# circuit.net
KiCad netlist of a schematic drawn in EAGLE
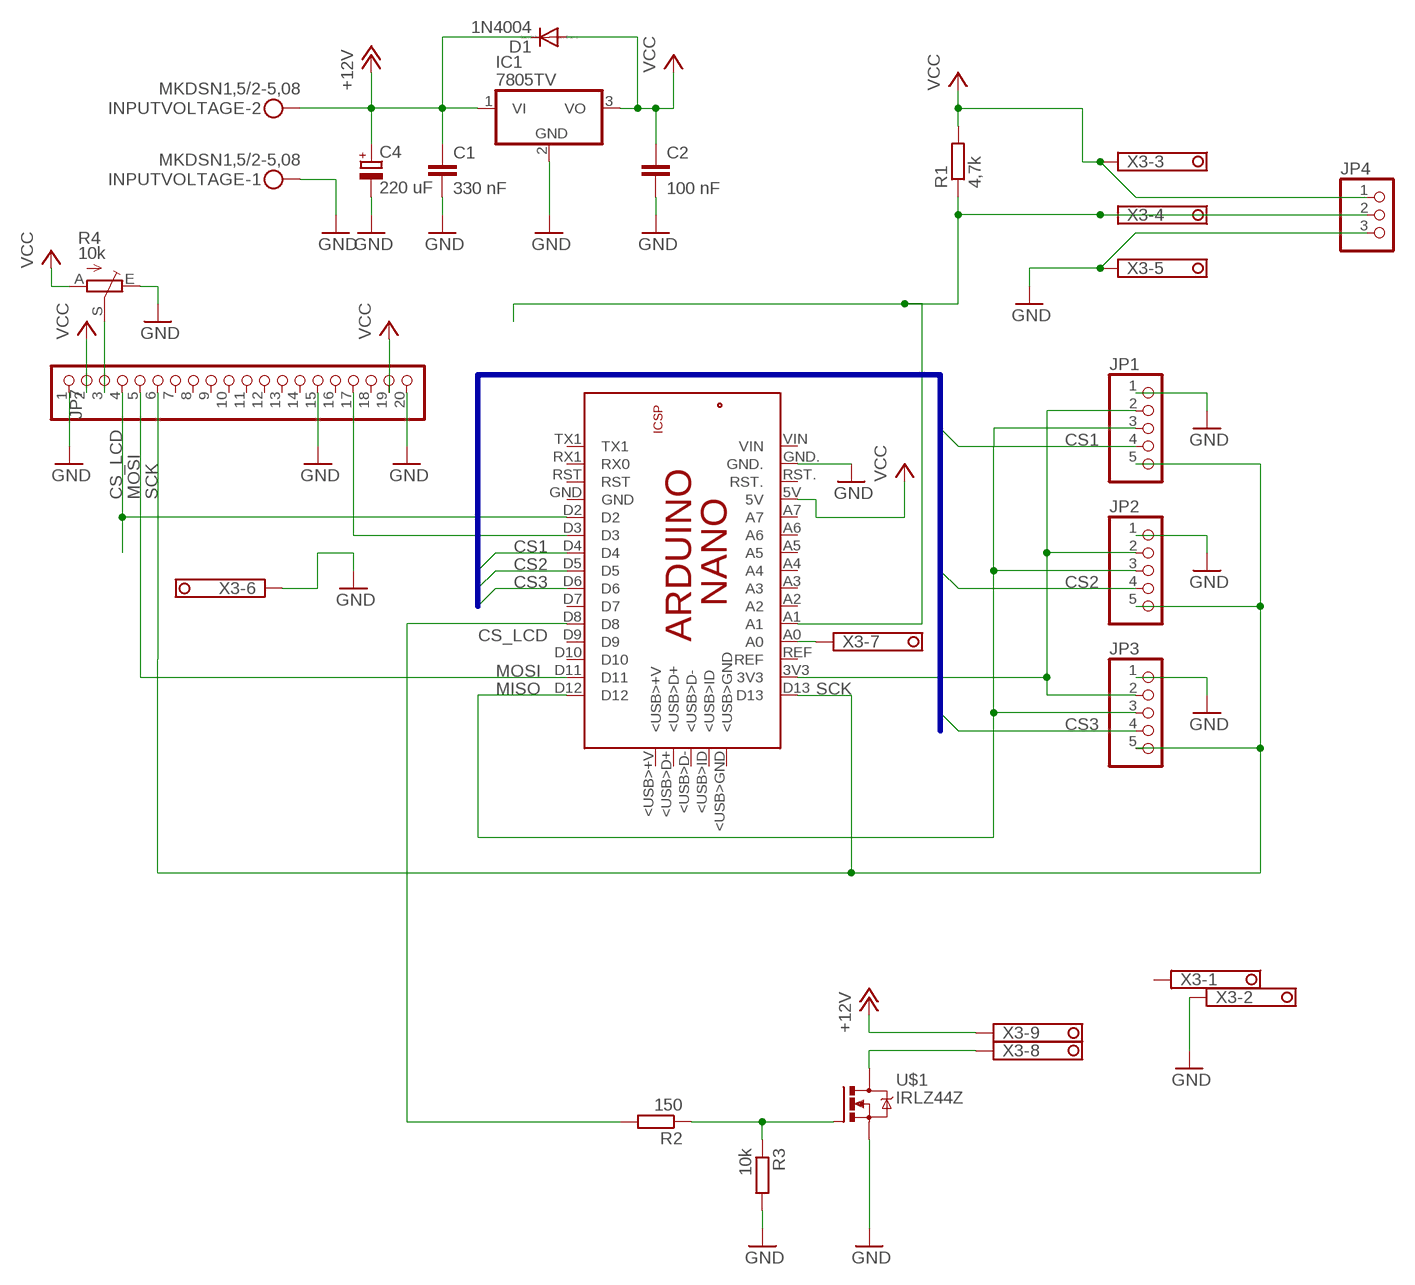
[diagram p0: schematic, sheet 1]

(export (version "E")
  (design (tool "Eeschema 10.0.6"))
  (components
    (comp (ref "C1")
      (value "330 nF")
      (footprint "eagle-import:C1206")
      (libsource (lib "eagle-import") (part "C-EUC1206"))
    )
    (comp (ref "C2")
      (value "100 nF")
      (footprint "eagle-import:C0603")
      (libsource (lib "eagle-import") (part "C-EUC0603"))
    )
    (comp (ref "C4")
      (value "220 uF")
      (footprint "eagle-import:E3,5-8")
      (libsource (lib "eagle-import") (part "CPOL-EUE3.5-8"))
    )
    (comp (ref "D1")
      (value "1N4004")
      (footprint "eagle-import:DO41-10")
      (libsource (lib "eagle-import") (part "1N4004"))
    )
    (comp (ref "IC1")
      (value "7805TV")
      (footprint "eagle-import:TO220V")
      (libsource (lib "eagle-import") (part "78TV05"))
    )
    (comp (ref "INPUTVOLTAGE")
      (value "MKDSN1,5/2-5,08")
      (footprint "eagle-import:MKDSN1,5_2-5,08")
      (libsource (lib "eagle-import") (part "MKDSN1,5/2-5,08"))
    )
    (comp (ref "JP1")
      (value "PINHD-1X5")
      (footprint "eagle-import:1X05")
      (libsource (lib "eagle-import") (part "PINHD-1X5"))
    )
    (comp (ref "JP2")
      (value "PINHD-1X5")
      (footprint "eagle-import:1X05")
      (libsource (lib "eagle-import") (part "PINHD-1X5"))
    )
    (comp (ref "JP3")
      (value "PINHD-1X5")
      (footprint "eagle-import:1X05")
      (libsource (lib "eagle-import") (part "PINHD-1X5"))
    )
    (comp (ref "JP4")
      (value "PINHD-1X3")
      (footprint "eagle-import:1X03")
      (libsource (lib "eagle-import") (part "PINHD-1X3"))
    )
    (comp (ref "JP7")
      (value "PINHD-1X20")
      (footprint "eagle-import:1X20")
      (libsource (lib "eagle-import") (part "PINHD-1X20"))
    )
    (comp (ref "PCB1")
      (value "ARDUINO_NANO")
      (footprint "eagle-import:ARDUINO_NANO")
      (libsource (lib "eagle-import") (part "ARDUINO_NANO"))
    )
    (comp (ref "R1")
      (value "4,7k")
      (footprint "eagle-import:0309_12")
      (libsource (lib "eagle-import") (part "R-EU_0309/12"))
    )
    (comp (ref "R2")
      (value "150")
      (footprint "eagle-import:0309_12")
      (libsource (lib "eagle-import") (part "R-EU_0309/12"))
    )
    (comp (ref "R3")
      (value "10k")
      (footprint "eagle-import:0309_12")
      (libsource (lib "eagle-import") (part "R-EU_0309/12"))
    )
    (comp (ref "R4")
      (value "10k")
      (footprint "eagle-import:B64Y")
      (libsource (lib "eagle-import") (part "TRIM_EU-B64Y"))
    )
    (comp (ref "U$1")
      (value "IRLZ44Z")
      (footprint "eagle-import:TO220BH")
      (libsource (lib "eagle-import") (part "IRLZ44Z"))
    )
    (comp (ref "X3")
      (value "1751316")
      (footprint "eagle-import:1751316")
      (libsource (lib "eagle-import") (part "1751316"))
    )
  )
  (nets
    (net (code "1") (name "+12V") (class "Default")
      (node (ref "C1") (pin "1") (pinfunction "1_1") (pintype "passive"))
      (node (ref "C4") (pin "+") (pinfunction "+_+") (pintype "passive"))
      (node (ref "D1") (pin "C") (pinfunction "C_C") (pintype "passive"))
      (node (ref "IC1") (pin "1") (pinfunction "VI_1") (pintype "input"))
      (node (ref "INPUTVOLTAGE") (pin "2") (pinfunction "KL_2") (pintype "passive"))
      (node (ref "X3") (pin "9") (pinfunction "K_9") (pintype "passive"))
    )
    (net (code "2") (name "/CS1") (class "Default")
      (node (ref "JP1") (pin "4") (pinfunction "4_4") (pintype "passive"))
      (node (ref "PCB1") (pin "D4") (pinfunction "D4_D4") (pintype "bidirectional"))
    )
    (net (code "3") (name "/CS2") (class "Default")
      (node (ref "JP2") (pin "4") (pinfunction "4_4") (pintype "passive"))
      (node (ref "PCB1") (pin "D5") (pinfunction "D5_D5") (pintype "bidirectional"))
    )
    (net (code "4") (name "/CS3") (class "Default")
      (node (ref "JP3") (pin "4") (pinfunction "4_4") (pintype "passive"))
      (node (ref "PCB1") (pin "D6") (pinfunction "D6_D6") (pintype "bidirectional"))
    )
    (net (code "5") (name "/CS_LCD") (class "Default")
      (node (ref "JP7") (pin "4") (pinfunction "4_4") (pintype "passive"))
      (node (ref "PCB1") (pin "D2") (pinfunction "D2_D2") (pintype "bidirectional"))
    )
    (net (code "6") (name "/MISO") (class "Default")
      (node (ref "JP1") (pin "3") (pinfunction "3_3") (pintype "passive"))
      (node (ref "JP2") (pin "3") (pinfunction "3_3") (pintype "passive"))
      (node (ref "JP3") (pin "3") (pinfunction "3_3") (pintype "passive"))
      (node (ref "PCB1") (pin "D12") (pinfunction "D12_D12") (pintype "bidirectional"))
    )
    (net (code "7") (name "/MOSI") (class "Default")
      (node (ref "JP7") (pin "5") (pinfunction "5_5") (pintype "passive"))
      (node (ref "PCB1") (pin "D11") (pinfunction "D11_D11") (pintype "bidirectional"))
    )
    (net (code "8") (name "/SCK") (class "Default")
      (node (ref "JP1") (pin "5") (pinfunction "5_5") (pintype "passive"))
      (node (ref "JP2") (pin "5") (pinfunction "5_5") (pintype "passive"))
      (node (ref "JP3") (pin "5") (pinfunction "5_5") (pintype "passive"))
      (node (ref "JP7") (pin "6") (pinfunction "6_6") (pintype "passive"))
      (node (ref "PCB1") (pin "D13") (pinfunction "D13_D13") (pintype "bidirectional"))
    )
    (net (code "9") (name "GND") (class "Default")
      (node (ref "C1") (pin "2") (pinfunction "2_2") (pintype "passive"))
      (node (ref "C2") (pin "2") (pinfunction "2_2") (pintype "passive"))
      (node (ref "C4") (pin "-") (pinfunction "-_-") (pintype "passive"))
      (node (ref "IC1") (pin "2") (pinfunction "GND_2") (pintype "passive"))
      (node (ref "INPUTVOLTAGE") (pin "1") (pinfunction "KL_1") (pintype "passive"))
      (node (ref "JP1") (pin "1") (pinfunction "1_1") (pintype "passive"))
      (node (ref "JP2") (pin "1") (pinfunction "1_1") (pintype "passive"))
      (node (ref "JP3") (pin "1") (pinfunction "1_1") (pintype "passive"))
      (node (ref "JP4") (pin "3") (pinfunction "3_3") (pintype "passive"))
      (node (ref "JP7") (pin "1") (pinfunction "1_1") (pintype "passive"))
      (node (ref "JP7") (pin "15") (pinfunction "15_15") (pintype "passive"))
      (node (ref "JP7") (pin "20") (pinfunction "20_20") (pintype "passive"))
      (node (ref "PCB1") (pin "GND.") (pinfunction "GND._GND.") (pintype "bidirectional"))
      (node (ref "R3") (pin "2") (pinfunction "2_2") (pintype "passive"))
      (node (ref "R4") (pin "E") (pinfunction "E_E") (pintype "passive"))
      (node (ref "U$1") (pin "S") (pinfunction "S_S") (pintype "passive"))
      (node (ref "X3") (pin "2") (pinfunction "K_2") (pintype "passive"))
      (node (ref "X3") (pin "5") (pinfunction "K_5") (pintype "passive"))
      (node (ref "X3") (pin "6") (pinfunction "K_6") (pintype "passive"))
    )
    (net (code "10") (name "Net-(JP1-Pad2)") (class "Default")
      (node (ref "JP1") (pin "2") (pinfunction "2_2") (pintype "passive"))
      (node (ref "JP2") (pin "2") (pinfunction "2_2") (pintype "passive"))
      (node (ref "JP3") (pin "2") (pinfunction "2_2") (pintype "passive"))
      (node (ref "PCB1") (pin "3V3") (pinfunction "3V3_3V3") (pintype "bidirectional"))
    )
    (net (code "11") (name "Net-(JP7-Pad3)") (class "Default")
      (node (ref "JP7") (pin "3") (pinfunction "3_3") (pintype "passive"))
      (node (ref "R4") (pin "S") (pinfunction "S_S") (pintype "passive"))
    )
    (net (code "12") (name "Net-(JP7-Pad17)") (class "Default")
      (node (ref "JP7") (pin "17") (pinfunction "17_17") (pintype "passive"))
      (node (ref "PCB1") (pin "D3") (pinfunction "D3_D3") (pintype "bidirectional"))
    )
    (net (code "13") (name "Net-(PCB1-PadD8)") (class "Default")
      (node (ref "PCB1") (pin "D8") (pinfunction "D8_D8") (pintype "bidirectional"))
      (node (ref "R2") (pin "2") (pinfunction "2_2") (pintype "passive"))
    )
    (net (code "14") (name "Net-(R2-Pad1)") (class "Default")
      (node (ref "R2") (pin "1") (pinfunction "1_1") (pintype "passive"))
      (node (ref "R3") (pin "1") (pinfunction "1_1") (pintype "passive"))
      (node (ref "U$1") (pin "G") (pinfunction "G_G") (pintype "passive"))
    )
    (net (code "15") (name "Net-(X3D-K)") (class "Default")
      (node (ref "JP4") (pin "2") (pinfunction "2_2") (pintype "passive"))
      (node (ref "PCB1") (pin "A1") (pinfunction "A1_A1") (pintype "bidirectional"))
      (node (ref "R1") (pin "1") (pinfunction "1_1") (pintype "passive"))
      (node (ref "X3") (pin "4") (pinfunction "K_4") (pintype "passive"))
    )
    (net (code "16") (name "Net-(X3G-K)") (class "Default")
      (node (ref "PCB1") (pin "A0") (pinfunction "A0_A0") (pintype "bidirectional"))
      (node (ref "X3") (pin "7") (pinfunction "K_7") (pintype "passive"))
    )
    (net (code "17") (name "Net-(X3H-K)") (class "Default")
      (node (ref "U$1") (pin "D") (pinfunction "D_D") (pintype "passive"))
      (node (ref "X3") (pin "8") (pinfunction "K_8") (pintype "passive"))
    )
    (net (code "18") (name "VCC") (class "Default")
      (node (ref "C2") (pin "1") (pinfunction "1_1") (pintype "passive"))
      (node (ref "D1") (pin "A") (pinfunction "A_A") (pintype "passive"))
      (node (ref "IC1") (pin "3") (pinfunction "VO_3") (pintype "passive"))
      (node (ref "JP4") (pin "1") (pinfunction "1_1") (pintype "passive"))
      (node (ref "JP7") (pin "19") (pinfunction "19_19") (pintype "passive"))
      (node (ref "JP7") (pin "2") (pinfunction "2_2") (pintype "passive"))
      (node (ref "PCB1") (pin "5V") (pinfunction "5V_5V") (pintype "bidirectional"))
      (node (ref "R1") (pin "2") (pinfunction "2_2") (pintype "passive"))
      (node (ref "R4") (pin "A") (pinfunction "A_A") (pintype "passive"))
      (node (ref "X3") (pin "3") (pinfunction "K_3") (pintype "passive"))
    )
    (net (code "19") (name "unconnected-(JP7-Pad7)") (class "Default")
      (node (ref "JP7") (pin "7") (pinfunction "7_7") (pintype "passive"))
    )
    (net (code "20") (name "unconnected-(JP7-Pad8)") (class "Default")
      (node (ref "JP7") (pin "8") (pinfunction "8_8") (pintype "passive"))
    )
    (net (code "21") (name "unconnected-(JP7-Pad9)") (class "Default")
      (node (ref "JP7") (pin "9") (pinfunction "9_9") (pintype "passive"))
    )
    (net (code "22") (name "unconnected-(JP7-Pad10)") (class "Default")
      (node (ref "JP7") (pin "10") (pinfunction "10_10") (pintype "passive"))
    )
    (net (code "23") (name "unconnected-(JP7-Pad11)") (class "Default")
      (node (ref "JP7") (pin "11") (pinfunction "11_11") (pintype "passive"))
    )
    (net (code "24") (name "unconnected-(JP7-Pad12)") (class "Default")
      (node (ref "JP7") (pin "12") (pinfunction "12_12") (pintype "passive"))
    )
    (net (code "25") (name "unconnected-(JP7-Pad13)") (class "Default")
      (node (ref "JP7") (pin "13") (pinfunction "13_13") (pintype "passive"))
    )
    (net (code "26") (name "unconnected-(JP7-Pad14)") (class "Default")
      (node (ref "JP7") (pin "14") (pinfunction "14_14") (pintype "passive"))
    )
    (net (code "27") (name "unconnected-(JP7-Pad16)") (class "Default")
      (node (ref "JP7") (pin "16") (pinfunction "16_16") (pintype "passive"))
    )
    (net (code "28") (name "unconnected-(JP7-Pad18)") (class "Default")
      (node (ref "JP7") (pin "18") (pinfunction "18_18") (pintype "passive"))
    )
    (net (code "29") (name "unconnected-(PCB1-Pad5V.)") (class "Default")
      (node (ref "PCB1") (pin "5V.") (pinfunction "5V._5V.") (pintype "bidirectional"))
    )
    (net (code "30") (name "unconnected-(PCB1-Pad<USB>+V)") (class "Default")
      (node (ref "PCB1") (pin "<USB>+V") (pinfunction "<USB>+V_<USB>+V") (pintype "bidirectional"))
    )
    (net (code "31") (name "unconnected-(PCB1-Pad<USB>D+)") (class "Default")
      (node (ref "PCB1") (pin "<USB>D+") (pinfunction "<USB>D+_<USB>D+") (pintype "bidirectional"))
    )
    (net (code "32") (name "unconnected-(PCB1-Pad<USB>D-)") (class "Default")
      (node (ref "PCB1") (pin "<USB>D-") (pinfunction "<USB>D-_<USB>D-") (pintype "bidirectional"))
    )
    (net (code "33") (name "unconnected-(PCB1-Pad<USB>GND)") (class "Default")
      (node (ref "PCB1") (pin "<USB>GND") (pinfunction "<USB>GND_<USB>GND") (pintype "bidirectional"))
    )
    (net (code "34") (name "unconnected-(PCB1-Pad<USB>ID)") (class "Default")
      (node (ref "PCB1") (pin "<USB>ID") (pinfunction "<USB>ID_<USB>ID") (pintype "bidirectional"))
    )
    (net (code "35") (name "unconnected-(PCB1-PadA2)") (class "Default")
      (node (ref "PCB1") (pin "A2") (pinfunction "A2_A2") (pintype "bidirectional"))
    )
    (net (code "36") (name "unconnected-(PCB1-PadA3)") (class "Default")
      (node (ref "PCB1") (pin "A3") (pinfunction "A3_A3") (pintype "bidirectional"))
    )
    (net (code "37") (name "unconnected-(PCB1-PadA4)") (class "Default")
      (node (ref "PCB1") (pin "A4") (pinfunction "A4_A4") (pintype "bidirectional"))
    )
    (net (code "38") (name "unconnected-(PCB1-PadA5)") (class "Default")
      (node (ref "PCB1") (pin "A5") (pinfunction "A5_A5") (pintype "bidirectional"))
    )
    (net (code "39") (name "unconnected-(PCB1-PadA6)") (class "Default")
      (node (ref "PCB1") (pin "A6") (pinfunction "A6_A6") (pintype "bidirectional"))
    )
    (net (code "40") (name "unconnected-(PCB1-PadA7)") (class "Default")
      (node (ref "PCB1") (pin "A7") (pinfunction "A7_A7") (pintype "bidirectional"))
    )
    (net (code "41") (name "unconnected-(PCB1-PadD7)") (class "Default")
      (node (ref "PCB1") (pin "D7") (pinfunction "D7_D7") (pintype "bidirectional"))
    )
    (net (code "42") (name "unconnected-(PCB1-PadD9)") (class "Default")
      (node (ref "PCB1") (pin "D9") (pinfunction "D9_D9") (pintype "bidirectional"))
    )
    (net (code "43") (name "unconnected-(PCB1-PadD10)") (class "Default")
      (node (ref "PCB1") (pin "D10") (pinfunction "D10_D10") (pintype "bidirectional"))
    )
    (net (code "44") (name "unconnected-(PCB1-PadGND)") (class "Default")
      (node (ref "PCB1") (pin "GND") (pinfunction "GND_GND") (pintype "bidirectional"))
    )
    (net (code "45") (name "unconnected-(PCB1-PadGND_)") (class "Default")
      (node (ref "PCB1") (pin "GND_") (pinfunction "GND__GND_") (pintype "bidirectional"))
    )
    (net (code "46") (name "unconnected-(PCB1-PadMISO)") (class "Default")
      (node (ref "PCB1") (pin "MISO") (pinfunction "MISO_MISO") (pintype "bidirectional"))
    )
    (net (code "47") (name "unconnected-(PCB1-PadMOSI)") (class "Default")
      (node (ref "PCB1") (pin "MOSI") (pinfunction "MOSI_MOSI") (pintype "bidirectional"))
    )
    (net (code "48") (name "unconnected-(PCB1-PadREF)") (class "Default")
      (node (ref "PCB1") (pin "REF") (pinfunction "REF_REF") (pintype "bidirectional"))
    )
    (net (code "49") (name "unconnected-(PCB1-PadRESET..)") (class "Default")
      (node (ref "PCB1") (pin "RESET..") (pinfunction "RESET.._RESET..") (pintype "bidirectional"))
    )
    (net (code "50") (name "unconnected-(PCB1-PadRST)") (class "Default")
      (node (ref "PCB1") (pin "RST") (pinfunction "RST_RST") (pintype "bidirectional"))
    )
    (net (code "51") (name "unconnected-(PCB1-PadRST.)") (class "Default")
      (node (ref "PCB1") (pin "RST.") (pinfunction "RST._RST.") (pintype "bidirectional"))
    )
    (net (code "52") (name "unconnected-(PCB1-PadSCK)") (class "Default")
      (node (ref "PCB1") (pin "SCK") (pinfunction "SCK_SCK") (pintype "bidirectional"))
    )
    (net (code "53") (name "unconnected-(PCB1-PadTX1)") (class "Default")
      (node (ref "PCB1") (pin "TX1") (pinfunction "TX1_TX1") (pintype "bidirectional"))
    )
    (net (code "54") (name "unconnected-(PCB1-PadVIN)") (class "Default")
      (node (ref "PCB1") (pin "VIN") (pinfunction "VIN_VIN") (pintype "bidirectional"))
    )
    (net (code "55") (name "unconnected-(PCB1-RX0-PadRX1)") (class "Default")
      (node (ref "PCB1") (pin "RX1") (pinfunction "RX0_RX1") (pintype "bidirectional"))
    )
    (net (code "56") (name "unconnected-(X3A-K-Pad1)") (class "Default")
      (node (ref "X3") (pin "1") (pinfunction "K_1") (pintype "passive"))
    )
  )
)
